# new.net
KiCad netlist of a schematic drawn in EAGLE
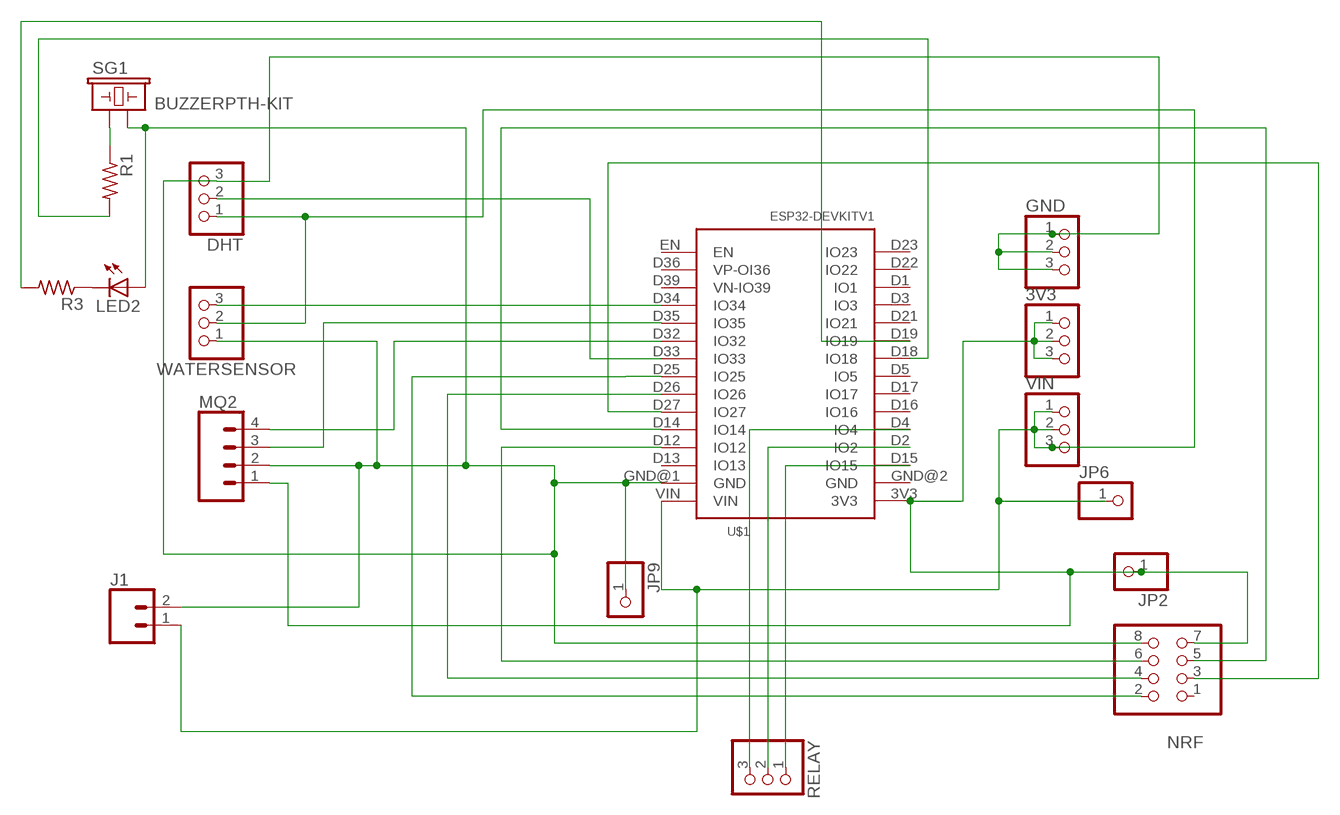
[diagram p0: schematic, sheet 1]

(export (version "E")
  (design (tool "Eeschema 10.0.6"))
  (components
    (comp (ref "3V3")
      (value "PINHD-1X3")
      (footprint "eagle-import:1X03")
      (libsource (lib "eagle-import") (part "PINHD-1X3"))
    )
    (comp (ref "DHT")
      (value "PINHD-1X3")
      (footprint "eagle-import:1X03")
      (libsource (lib "eagle-import") (part "PINHD-1X3"))
    )
    (comp (ref "GND")
      (value "PINHD-1X3")
      (footprint "eagle-import:1X03")
      (libsource (lib "eagle-import") (part "PINHD-1X3"))
    )
    (comp (ref "J1")
      (value "CONN_02")
      (footprint "eagle-import:1X02")
      (libsource (lib "eagle-import") (part "CONN_02"))
    )
    (comp (ref "JP2")
      (value "PINHD-1X1")
      (footprint "eagle-import:1X01")
      (libsource (lib "eagle-import") (part "PINHD-1X1"))
    )
    (comp (ref "JP6")
      (value "PINHD-1X1")
      (footprint "eagle-import:1X01")
      (libsource (lib "eagle-import") (part "PINHD-1X1"))
    )
    (comp (ref "JP9")
      (value "PINHD-1X1")
      (footprint "eagle-import:1X01")
      (libsource (lib "eagle-import") (part "PINHD-1X1"))
    )
    (comp (ref "LED2")
      (value "LED5MM")
      (footprint "eagle-import:LED5MM")
      (libsource (lib "eagle-import") (part "LED5MM"))
    )
    (comp (ref "MQ2")
      (value "CONN_04PTH")
      (footprint "eagle-import:1X04")
      (libsource (lib "eagle-import") (part "CONN_04PTH"))
    )
    (comp (ref "NRF")
      (value "PINHD-2X4")
      (footprint "eagle-import:2X04")
      (libsource (lib "eagle-import") (part "PINHD-2X4"))
    )
    (comp (ref "R1")
      (value "R-US_0207/7")
      (footprint "eagle-import:0207_7")
      (libsource (lib "eagle-import") (part "R-US_0207/7"))
    )
    (comp (ref "R3")
      (value "R-US_0207/7")
      (footprint "eagle-import:0207_7")
      (libsource (lib "eagle-import") (part "R-US_0207/7"))
    )
    (comp (ref "RELAY")
      (value "PINHD-1X3")
      (footprint "eagle-import:1X03")
      (libsource (lib "eagle-import") (part "PINHD-1X3"))
    )
    (comp (ref "SG1")
      (value "BUZZERPTH-KIT")
      (footprint "eagle-import:BUZZER-12MM-KIT")
      (libsource (lib "eagle-import") (part "BUZZERPTH-KIT"))
    )
    (comp (ref "U$1")
      (value "ESP32DEVKITV1")
      (footprint "eagle-import:ESP32-DEVKITV1")
      (libsource (lib "eagle-import") (part "ESP32DEVKITV1"))
    )
    (comp (ref "VIN")
      (value "PINHD-1X3")
      (footprint "eagle-import:1X03")
      (libsource (lib "eagle-import") (part "PINHD-1X3"))
    )
    (comp (ref "WATERSENSOR")
      (value "PINHD-1X3")
      (footprint "eagle-import:1X03")
      (libsource (lib "eagle-import") (part "PINHD-1X3"))
    )
  )
  (nets
    (net (code "1") (name "Net-(3V3-Pad1)") (class "Default")
      (node (ref "3V3") (pin "1") (pinfunction "1_1") (pintype "passive"))
      (node (ref "3V3") (pin "2") (pinfunction "2_2") (pintype "passive"))
      (node (ref "3V3") (pin "3") (pinfunction "3_3") (pintype "passive"))
      (node (ref "JP2") (pin "1") (pinfunction "1_1") (pintype "passive"))
      (node (ref "MQ2") (pin "1") (pinfunction "1_1") (pintype "passive"))
      (node (ref "NRF") (pin "7") (pinfunction "7_7") (pintype "passive"))
      (node (ref "U$1") (pin "3V3") (pinfunction "3V3_3V3") (pintype "bidirectional"))
    )
    (net (code "2") (name "Net-(DHT-Pad1)") (class "Default")
      (node (ref "DHT") (pin "1") (pinfunction "1_1") (pintype "passive"))
      (node (ref "J1") (pin "1") (pinfunction "1_1") (pintype "passive"))
      (node (ref "JP6") (pin "1") (pinfunction "1_1") (pintype "passive"))
      (node (ref "U$1") (pin "VIN") (pinfunction "VIN_VIN") (pintype "bidirectional"))
      (node (ref "VIN") (pin "1") (pinfunction "1_1") (pintype "passive"))
      (node (ref "VIN") (pin "2") (pinfunction "2_2") (pintype "passive"))
      (node (ref "VIN") (pin "3") (pinfunction "3_3") (pintype "passive"))
      (node (ref "WATERSENSOR") (pin "2") (pinfunction "2_2") (pintype "passive"))
    )
    (net (code "3") (name "Net-(LED2-C)") (class "Default")
      (node (ref "LED2") (pin "K") (pinfunction "C_K") (pintype "passive"))
      (node (ref "R3") (pin "1") (pinfunction "1_1") (pintype "passive"))
    )
    (net (code "4") (name "Net-(SG1-1)") (class "Default")
      (node (ref "R1") (pin "1") (pinfunction "1_1") (pintype "passive"))
      (node (ref "SG1") (pin "+") (pinfunction "1_+") (pintype "passive"))
    )
    (net (code "5") (name "Net-(SG1-2)") (class "Default")
      (node (ref "DHT") (pin "3") (pinfunction "3_3") (pintype "passive"))
      (node (ref "GND") (pin "1") (pinfunction "1_1") (pintype "passive"))
      (node (ref "GND") (pin "2") (pinfunction "2_2") (pintype "passive"))
      (node (ref "GND") (pin "3") (pinfunction "3_3") (pintype "passive"))
      (node (ref "J1") (pin "2") (pinfunction "2_2") (pintype "passive"))
      (node (ref "JP9") (pin "1") (pinfunction "1_1") (pintype "passive"))
      (node (ref "LED2") (pin "A") (pinfunction "A_A") (pintype "passive"))
      (node (ref "MQ2") (pin "2") (pinfunction "2_2") (pintype "passive"))
      (node (ref "NRF") (pin "8") (pinfunction "8_8") (pintype "passive"))
      (node (ref "SG1") (pin "-") (pinfunction "2_-") (pintype "passive"))
      (node (ref "U$1") (pin "GND@1") (pinfunction "GND_GND@1") (pintype "bidirectional"))
      (node (ref "WATERSENSOR") (pin "1") (pinfunction "1_1") (pintype "passive"))
    )
    (net (code "6") (name "Net-(U$1-IO2)") (class "Default")
      (node (ref "RELAY") (pin "2") (pinfunction "2_2") (pintype "passive"))
      (node (ref "U$1") (pin "D2") (pinfunction "IO2_D2") (pintype "bidirectional"))
    )
    (net (code "7") (name "Net-(U$1-IO4)") (class "Default")
      (node (ref "RELAY") (pin "3") (pinfunction "3_3") (pintype "passive"))
      (node (ref "U$1") (pin "D4") (pinfunction "IO4_D4") (pintype "bidirectional"))
    )
    (net (code "8") (name "Net-(U$1-IO12)") (class "Default")
      (node (ref "NRF") (pin "6") (pinfunction "6_6") (pintype "passive"))
      (node (ref "U$1") (pin "D12") (pinfunction "IO12_D12") (pintype "bidirectional"))
    )
    (net (code "9") (name "Net-(U$1-IO14)") (class "Default")
      (node (ref "NRF") (pin "5") (pinfunction "5_5") (pintype "passive"))
      (node (ref "U$1") (pin "D14") (pinfunction "IO14_D14") (pintype "bidirectional"))
    )
    (net (code "10") (name "Net-(U$1-IO15)") (class "Default")
      (node (ref "RELAY") (pin "1") (pinfunction "1_1") (pintype "passive"))
      (node (ref "U$1") (pin "D15") (pinfunction "IO15_D15") (pintype "bidirectional"))
    )
    (net (code "11") (name "Net-(U$1-IO18)") (class "Default")
      (node (ref "R1") (pin "2") (pinfunction "2_2") (pintype "passive"))
      (node (ref "U$1") (pin "D18") (pinfunction "IO18_D18") (pintype "bidirectional"))
    )
    (net (code "12") (name "Net-(U$1-IO19)") (class "Default")
      (node (ref "R3") (pin "2") (pinfunction "2_2") (pintype "passive"))
      (node (ref "U$1") (pin "D19") (pinfunction "IO19_D19") (pintype "bidirectional"))
    )
    (net (code "13") (name "Net-(U$1-IO25)") (class "Default")
      (node (ref "NRF") (pin "2") (pinfunction "2_2") (pintype "passive"))
      (node (ref "U$1") (pin "D25") (pinfunction "IO25_D25") (pintype "bidirectional"))
    )
    (net (code "14") (name "Net-(U$1-IO26)") (class "Default")
      (node (ref "NRF") (pin "4") (pinfunction "4_4") (pintype "passive"))
      (node (ref "U$1") (pin "D26") (pinfunction "IO26_D26") (pintype "bidirectional"))
    )
    (net (code "15") (name "Net-(U$1-IO27)") (class "Default")
      (node (ref "NRF") (pin "3") (pinfunction "3_3") (pintype "passive"))
      (node (ref "U$1") (pin "D27") (pinfunction "IO27_D27") (pintype "bidirectional"))
    )
    (net (code "16") (name "Net-(U$1-IO32)") (class "Default")
      (node (ref "MQ2") (pin "4") (pinfunction "4_4") (pintype "passive"))
      (node (ref "U$1") (pin "D32") (pinfunction "IO32_D32") (pintype "bidirectional"))
    )
    (net (code "17") (name "Net-(U$1-IO33)") (class "Default")
      (node (ref "DHT") (pin "2") (pinfunction "2_2") (pintype "passive"))
      (node (ref "U$1") (pin "D33") (pinfunction "IO33_D33") (pintype "bidirectional"))
    )
    (net (code "18") (name "Net-(U$1-IO34)") (class "Default")
      (node (ref "U$1") (pin "D34") (pinfunction "IO34_D34") (pintype "bidirectional"))
      (node (ref "WATERSENSOR") (pin "3") (pinfunction "3_3") (pintype "passive"))
    )
    (net (code "19") (name "Net-(U$1-IO35)") (class "Default")
      (node (ref "MQ2") (pin "3") (pinfunction "3_3") (pintype "passive"))
      (node (ref "U$1") (pin "D35") (pinfunction "IO35_D35") (pintype "bidirectional"))
    )
    (net (code "20") (name "unconnected-(NRF-Pad1)") (class "Default")
      (node (ref "NRF") (pin "1") (pinfunction "1_1") (pintype "passive"))
    )
    (net (code "21") (name "unconnected-(U$1-GND-PadGND@2)") (class "Default")
      (node (ref "U$1") (pin "GND@2") (pinfunction "GND_GND@2") (pintype "bidirectional"))
    )
    (net (code "22") (name "unconnected-(U$1-IO1-PadD1)") (class "Default")
      (node (ref "U$1") (pin "D1") (pinfunction "IO1_D1") (pintype "bidirectional"))
    )
    (net (code "23") (name "unconnected-(U$1-IO3-PadD3)") (class "Default")
      (node (ref "U$1") (pin "D3") (pinfunction "IO3_D3") (pintype "bidirectional"))
    )
    (net (code "24") (name "unconnected-(U$1-IO5-PadD5)") (class "Default")
      (node (ref "U$1") (pin "D5") (pinfunction "IO5_D5") (pintype "bidirectional"))
    )
    (net (code "25") (name "unconnected-(U$1-IO13-PadD13)") (class "Default")
      (node (ref "U$1") (pin "D13") (pinfunction "IO13_D13") (pintype "bidirectional"))
    )
    (net (code "26") (name "unconnected-(U$1-IO16-PadD16)") (class "Default")
      (node (ref "U$1") (pin "D16") (pinfunction "IO16_D16") (pintype "bidirectional"))
    )
    (net (code "27") (name "unconnected-(U$1-IO17-PadD17)") (class "Default")
      (node (ref "U$1") (pin "D17") (pinfunction "IO17_D17") (pintype "bidirectional"))
    )
    (net (code "28") (name "unconnected-(U$1-IO21-PadD21)") (class "Default")
      (node (ref "U$1") (pin "D21") (pinfunction "IO21_D21") (pintype "bidirectional"))
    )
    (net (code "29") (name "unconnected-(U$1-IO22-PadD22)") (class "Default")
      (node (ref "U$1") (pin "D22") (pinfunction "IO22_D22") (pintype "bidirectional"))
    )
    (net (code "30") (name "unconnected-(U$1-IO23-PadD23)") (class "Default")
      (node (ref "U$1") (pin "D23") (pinfunction "IO23_D23") (pintype "bidirectional"))
    )
    (net (code "31") (name "unconnected-(U$1-PadEN)") (class "Default")
      (node (ref "U$1") (pin "EN") (pinfunction "EN_EN") (pintype "bidirectional"))
    )
    (net (code "32") (name "unconnected-(U$1-VN-IO39-PadD39)") (class "Default")
      (node (ref "U$1") (pin "D39") (pinfunction "VN-IO39_D39") (pintype "bidirectional"))
    )
    (net (code "33") (name "unconnected-(U$1-VP-OI36-PadD36)") (class "Default")
      (node (ref "U$1") (pin "D36") (pinfunction "VP-OI36_D36") (pintype "bidirectional"))
    )
  )
)
